# Delaytuning.net
KiCad netlist of a schematic drawn in Altium Designer
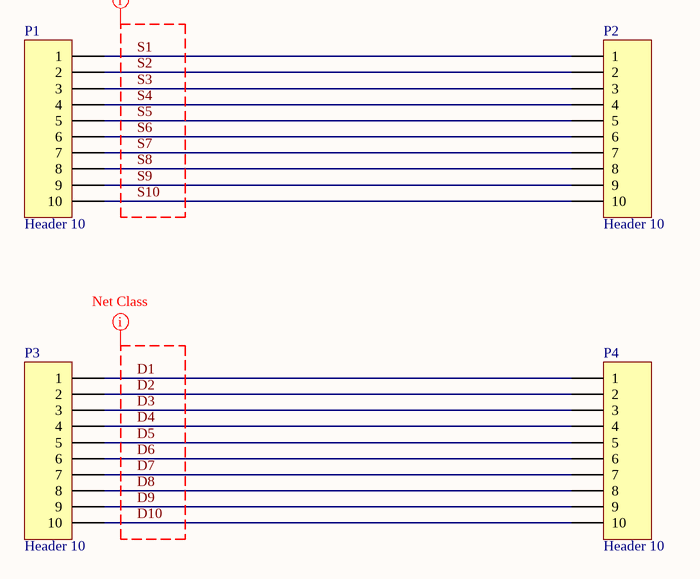
[diagram p0: Delaytuning.SchDoc]

(export (version "E")
  (design (tool "Eeschema 10.0.6"))
  (components
    (comp (ref "P1")
      (value "Header 10")
      (footprint "HDR1X10")
      (description "Header, 10-Pin")
      (fields (field (name "PUBLISHER") "Altium Limited"))
      (libsource (lib "Miscellaneous Connectors") (part "Header 10"))
    )
    (comp (ref "P2")
      (value "Header 10")
      (footprint "HDR1X10")
      (description "Header, 10-Pin")
      (fields (field (name "PUBLISHER") "Altium Limited"))
      (libsource (lib "") (part "Header 10_1"))
    )
    (comp (ref "P3")
      (value "Header 10")
      (footprint "HDR1X10")
      (description "Header, 10-Pin")
      (fields (field (name "PUBLISHER") "Altium Limited"))
      (libsource (lib "Miscellaneous Connectors") (part "Header 10"))
    )
    (comp (ref "P4")
      (value "Header 10")
      (footprint "HDR1X10")
      (description "Header, 10-Pin")
      (fields (field (name "PUBLISHER") "Altium Limited"))
      (libsource (lib "") (part "Header 10_1"))
    )
  )
  (nets
    (net (code "1") (name "/D1") (class "Default")
      (node (ref "P3") (pin "1") (pinfunction "1_1") (pintype "passive"))
      (node (ref "P4") (pin "1") (pinfunction "1_1") (pintype "passive"))
    )
    (net (code "2") (name "/D2") (class "Default")
      (node (ref "P3") (pin "2") (pinfunction "2_2") (pintype "passive"))
      (node (ref "P4") (pin "2") (pinfunction "2_2") (pintype "passive"))
    )
    (net (code "3") (name "/D3") (class "Default")
      (node (ref "P3") (pin "3") (pinfunction "3_3") (pintype "passive"))
      (node (ref "P4") (pin "3") (pinfunction "3_3") (pintype "passive"))
    )
    (net (code "4") (name "/D4") (class "Default")
      (node (ref "P3") (pin "4") (pinfunction "4_4") (pintype "passive"))
      (node (ref "P4") (pin "4") (pinfunction "4_4") (pintype "passive"))
    )
    (net (code "5") (name "/D5") (class "Default")
      (node (ref "P3") (pin "5") (pinfunction "5_5") (pintype "passive"))
      (node (ref "P4") (pin "5") (pinfunction "5_5") (pintype "passive"))
    )
    (net (code "6") (name "/D6") (class "Default")
      (node (ref "P3") (pin "6") (pinfunction "6_6") (pintype "passive"))
      (node (ref "P4") (pin "6") (pinfunction "6_6") (pintype "passive"))
    )
    (net (code "7") (name "/D7") (class "Default")
      (node (ref "P3") (pin "7") (pinfunction "7_7") (pintype "passive"))
      (node (ref "P4") (pin "7") (pinfunction "7_7") (pintype "passive"))
    )
    (net (code "8") (name "/D8") (class "Default")
      (node (ref "P3") (pin "8") (pinfunction "8_8") (pintype "passive"))
      (node (ref "P4") (pin "8") (pinfunction "8_8") (pintype "passive"))
    )
    (net (code "9") (name "/D9") (class "Default")
      (node (ref "P3") (pin "9") (pinfunction "9_9") (pintype "passive"))
      (node (ref "P4") (pin "9") (pinfunction "9_9") (pintype "passive"))
    )
    (net (code "10") (name "/D10") (class "Default")
      (node (ref "P3") (pin "10") (pinfunction "10_10") (pintype "passive"))
      (node (ref "P4") (pin "10") (pinfunction "10_10") (pintype "passive"))
    )
    (net (code "11") (name "/S1") (class "Default")
      (node (ref "P1") (pin "1") (pinfunction "1_1") (pintype "passive"))
      (node (ref "P2") (pin "1") (pinfunction "1_1") (pintype "passive"))
    )
    (net (code "12") (name "/S2") (class "Default")
      (node (ref "P1") (pin "2") (pinfunction "2_2") (pintype "passive"))
      (node (ref "P2") (pin "2") (pinfunction "2_2") (pintype "passive"))
    )
    (net (code "13") (name "/S3") (class "Default")
      (node (ref "P1") (pin "3") (pinfunction "3_3") (pintype "passive"))
      (node (ref "P2") (pin "3") (pinfunction "3_3") (pintype "passive"))
    )
    (net (code "14") (name "/S4") (class "Default")
      (node (ref "P1") (pin "4") (pinfunction "4_4") (pintype "passive"))
      (node (ref "P2") (pin "4") (pinfunction "4_4") (pintype "passive"))
    )
    (net (code "15") (name "/S5") (class "Default")
      (node (ref "P1") (pin "5") (pinfunction "5_5") (pintype "passive"))
      (node (ref "P2") (pin "5") (pinfunction "5_5") (pintype "passive"))
    )
    (net (code "16") (name "/S6") (class "Default")
      (node (ref "P1") (pin "6") (pinfunction "6_6") (pintype "passive"))
      (node (ref "P2") (pin "6") (pinfunction "6_6") (pintype "passive"))
    )
    (net (code "17") (name "/S7") (class "Default")
      (node (ref "P1") (pin "7") (pinfunction "7_7") (pintype "passive"))
      (node (ref "P2") (pin "7") (pinfunction "7_7") (pintype "passive"))
    )
    (net (code "18") (name "/S8") (class "Default")
      (node (ref "P1") (pin "8") (pinfunction "8_8") (pintype "passive"))
      (node (ref "P2") (pin "8") (pinfunction "8_8") (pintype "passive"))
    )
    (net (code "19") (name "/S9") (class "Default")
      (node (ref "P1") (pin "9") (pinfunction "9_9") (pintype "passive"))
      (node (ref "P2") (pin "9") (pinfunction "9_9") (pintype "passive"))
    )
    (net (code "20") (name "/S10") (class "Default")
      (node (ref "P1") (pin "10") (pinfunction "10_10") (pintype "passive"))
      (node (ref "P2") (pin "10") (pinfunction "10_10") (pintype "passive"))
    )
  )
)
